# analog_adapter.net
KiCad netlist of a schematic drawn in EAGLE
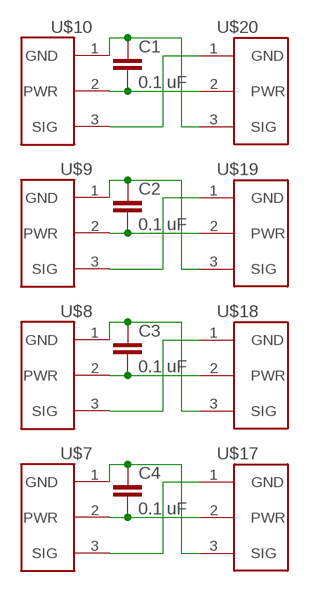
[diagram p0: schematic, sheet 1]

(export (version "E")
  (design (tool "Eeschema 10.0.6"))
  (components
    (comp (ref "C1")
      (value "0.1 uF")
      (footprint "eagle-import:0603")
      (libsource (lib "eagle-import") (part "CAP0603"))
    )
    (comp (ref "C2")
      (value "0.1 uF")
      (footprint "eagle-import:0603")
      (libsource (lib "eagle-import") (part "CAP0603"))
    )
    (comp (ref "C3")
      (value "0.1 uF")
      (footprint "eagle-import:0603")
      (libsource (lib "eagle-import") (part "CAP0603"))
    )
    (comp (ref "C4")
      (value "0.1 uF")
      (footprint "eagle-import:0603")
      (libsource (lib "eagle-import") (part "CAP0603"))
    )
    (comp (ref "U$7")
      (value "22-23-2031GENERIC")
      (footprint "eagle-import:PWM_1X3")
      (libsource (lib "eagle-import") (part "22-23-2031GENERIC"))
    )
    (comp (ref "U$8")
      (value "22-23-2031GENERIC")
      (footprint "eagle-import:PWM_1X3")
      (libsource (lib "eagle-import") (part "22-23-2031GENERIC"))
    )
    (comp (ref "U$9")
      (value "22-23-2031GENERIC")
      (footprint "eagle-import:PWM_1X3")
      (libsource (lib "eagle-import") (part "22-23-2031GENERIC"))
    )
    (comp (ref "U$10")
      (value "22-23-2031GENERIC")
      (footprint "eagle-import:PWM_1X3")
      (libsource (lib "eagle-import") (part "22-23-2031GENERIC"))
    )
    (comp (ref "U$17")
      (value "22-23-2031")
      (footprint "eagle-import:22-23-2031")
      (libsource (lib "eagle-import") (part "22-23-2031"))
    )
    (comp (ref "U$18")
      (value "22-23-2031")
      (footprint "eagle-import:22-23-2031")
      (libsource (lib "eagle-import") (part "22-23-2031"))
    )
    (comp (ref "U$19")
      (value "22-23-2031")
      (footprint "eagle-import:22-23-2031")
      (libsource (lib "eagle-import") (part "22-23-2031"))
    )
    (comp (ref "U$20")
      (value "22-23-2031")
      (footprint "eagle-import:22-23-2031")
      (libsource (lib "eagle-import") (part "22-23-2031"))
    )
  )
  (nets
    (net (code "1") (name "Net-(U$10-GND)") (class "Default")
      (node (ref "C1") (pin "1") (pinfunction "1_1") (pintype "passive"))
      (node (ref "U$10") (pin "1") (pinfunction "GND_1") (pintype "power_in"))
      (node (ref "U$20") (pin "3") (pinfunction "SIG_3") (pintype "bidirectional"))
    )
    (net (code "2") (name "Net-(U$10-PWR)") (class "Default")
      (node (ref "C1") (pin "2") (pinfunction "2_2") (pintype "passive"))
      (node (ref "U$10") (pin "2") (pinfunction "PWR_2") (pintype "power_in"))
      (node (ref "U$20") (pin "2") (pinfunction "PWR_2") (pintype "power_in"))
    )
    (net (code "3") (name "Net-(U$10-SIG)") (class "Default")
      (node (ref "U$10") (pin "3") (pinfunction "SIG_3") (pintype "bidirectional"))
      (node (ref "U$20") (pin "1") (pinfunction "GND_1") (pintype "power_in"))
    )
    (net (code "4") (name "Net-(U$17-GND)") (class "Default")
      (node (ref "U$17") (pin "1") (pinfunction "GND_1") (pintype "power_in"))
      (node (ref "U$7") (pin "3") (pinfunction "SIG_3") (pintype "bidirectional"))
    )
    (net (code "5") (name "Net-(U$17-PWR)") (class "Default")
      (node (ref "C4") (pin "2") (pinfunction "2_2") (pintype "passive"))
      (node (ref "U$17") (pin "2") (pinfunction "PWR_2") (pintype "power_in"))
      (node (ref "U$7") (pin "2") (pinfunction "PWR_2") (pintype "power_in"))
    )
    (net (code "6") (name "Net-(U$17-SIG)") (class "Default")
      (node (ref "C4") (pin "1") (pinfunction "1_1") (pintype "passive"))
      (node (ref "U$17") (pin "3") (pinfunction "SIG_3") (pintype "bidirectional"))
      (node (ref "U$7") (pin "1") (pinfunction "GND_1") (pintype "power_in"))
    )
    (net (code "7") (name "Net-(U$18-GND)") (class "Default")
      (node (ref "U$18") (pin "1") (pinfunction "GND_1") (pintype "power_in"))
      (node (ref "U$8") (pin "3") (pinfunction "SIG_3") (pintype "bidirectional"))
    )
    (net (code "8") (name "Net-(U$18-PWR)") (class "Default")
      (node (ref "C3") (pin "2") (pinfunction "2_2") (pintype "passive"))
      (node (ref "U$18") (pin "2") (pinfunction "PWR_2") (pintype "power_in"))
      (node (ref "U$8") (pin "2") (pinfunction "PWR_2") (pintype "power_in"))
    )
    (net (code "9") (name "Net-(U$18-SIG)") (class "Default")
      (node (ref "C3") (pin "1") (pinfunction "1_1") (pintype "passive"))
      (node (ref "U$18") (pin "3") (pinfunction "SIG_3") (pintype "bidirectional"))
      (node (ref "U$8") (pin "1") (pinfunction "GND_1") (pintype "power_in"))
    )
    (net (code "10") (name "Net-(U$19-GND)") (class "Default")
      (node (ref "U$19") (pin "1") (pinfunction "GND_1") (pintype "power_in"))
      (node (ref "U$9") (pin "3") (pinfunction "SIG_3") (pintype "bidirectional"))
    )
    (net (code "11") (name "Net-(U$19-PWR)") (class "Default")
      (node (ref "C2") (pin "2") (pinfunction "2_2") (pintype "passive"))
      (node (ref "U$19") (pin "2") (pinfunction "PWR_2") (pintype "power_in"))
      (node (ref "U$9") (pin "2") (pinfunction "PWR_2") (pintype "power_in"))
    )
    (net (code "12") (name "Net-(U$19-SIG)") (class "Default")
      (node (ref "C2") (pin "1") (pinfunction "1_1") (pintype "passive"))
      (node (ref "U$19") (pin "3") (pinfunction "SIG_3") (pintype "bidirectional"))
      (node (ref "U$9") (pin "1") (pinfunction "GND_1") (pintype "power_in"))
    )
  )
)
